# Halfbridge.net
KiCad netlist of a schematic drawn in Altium Designer
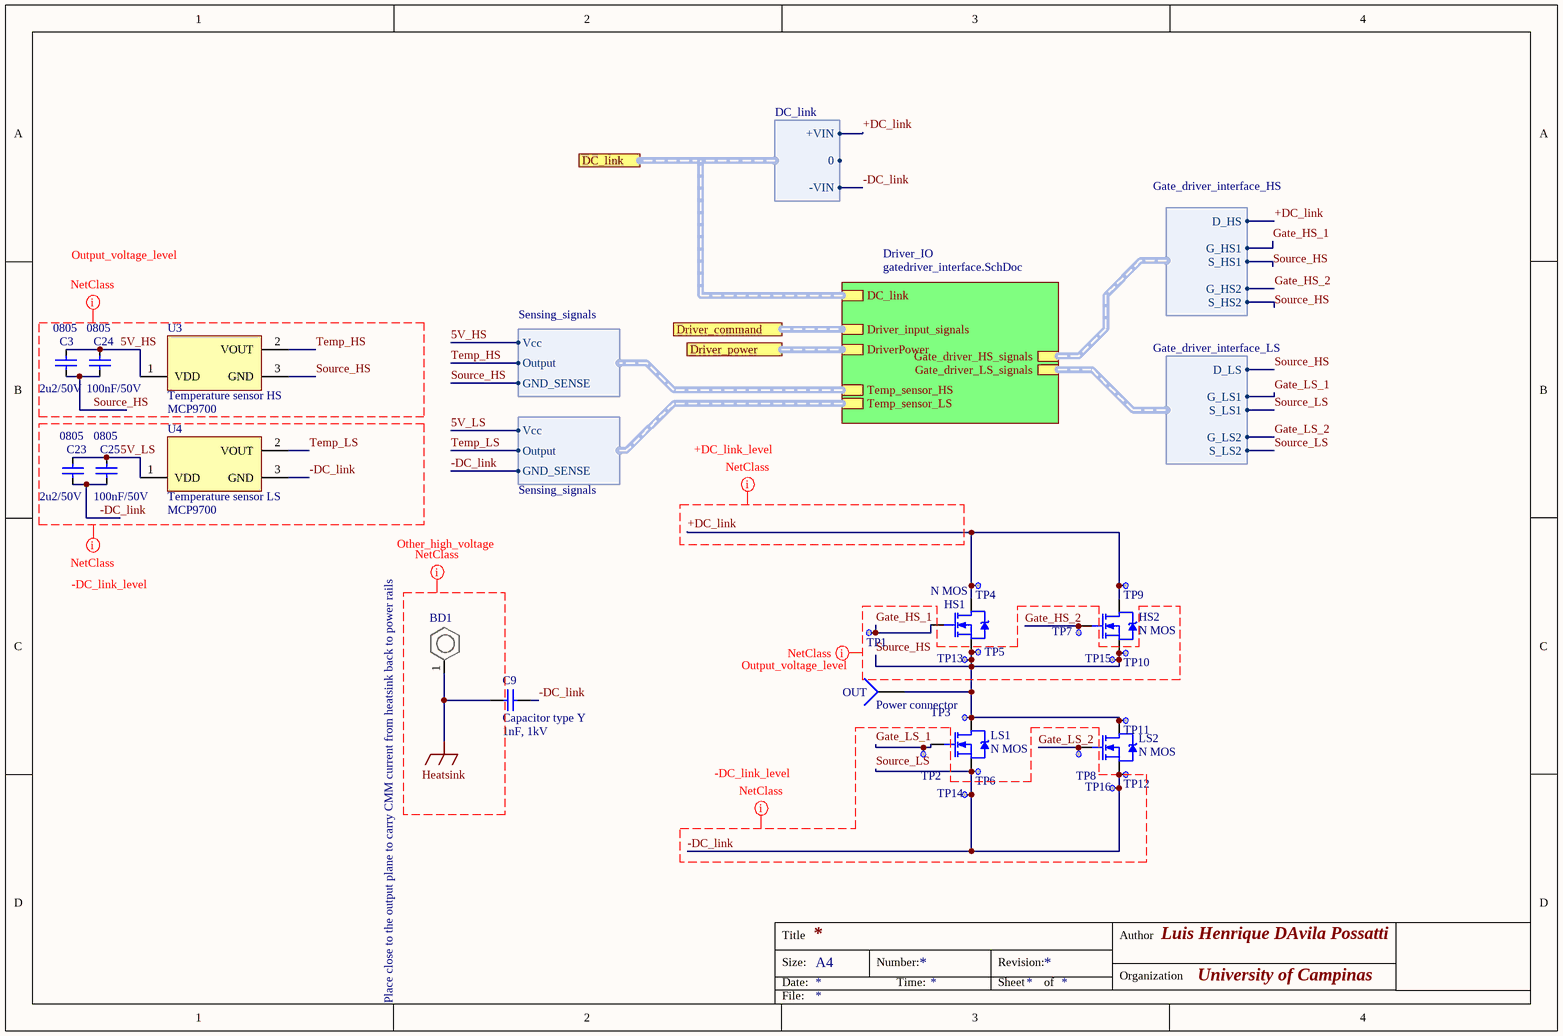
[diagram p0: Halfbridge.SchDoc]

(export (version "E")
  (design (tool "Eeschema 10.0.6"))
  (components
    (comp (ref "BD1")
      (value "Place near output plane")
      (footprint "Bonding_screw")
      (description "Used to connect the net to the heatsink below board")
      (libsource (lib "EdgeInverter_library") (part "Bonding_screw"))
    )
    (comp (ref "C3")
      (value "0805")
      (footprint "Capacitor 0805")
      (description "SMD ceramic capacitor 0805")
      (fields (field (name "ALTIUM_VALUE") "2u2/50V"))
      (libsource (lib "EdgeInverter_library") (part "Capacitor 0805"))
    )
    (comp (ref "C9")
      (value "Capacitor type Y")
      (footprint "CAPACITOR 1812")
      (description "High Voltage Capacitor to filter EMC from heatsink")
      (fields (field (name "ALTIUM_VALUE") "1nF, 1kV"))
      (libsource (lib "EdgeInverter_library") (part "Y Capacitor"))
    )
    (comp (ref "C23")
      (value "0805")
      (footprint "Capacitor 0805")
      (description "SMD ceramic capacitor 0805")
      (fields (field (name "ALTIUM_VALUE") "2u2/50V"))
      (libsource (lib "EdgeInverter_library") (part "Capacitor 0805"))
    )
    (comp (ref "C24")
      (value "0805")
      (footprint "Capacitor 0805")
      (description "SMD ceramic capacitor 0805")
      (fields (field (name "ALTIUM_VALUE") "100nF/50V"))
      (libsource (lib "EdgeInverter_library") (part "Capacitor 0805"))
    )
    (comp (ref "C25")
      (value "0805")
      (footprint "Capacitor 0805")
      (description "SMD ceramic capacitor 0805")
      (fields (field (name "ALTIUM_VALUE") "100nF/50V"))
      (libsource (lib "EdgeInverter_library") (part "Capacitor 0805"))
    )
    (comp (ref "HS1")
      (value "N MOS")
      (footprint "TO247 custom 4")
      (description "Power Mosfet N channel, TO-247, multiple part numbers")
      (libsource (lib "EdgeInverter_library") (part "MOSFET"))
    )
    (comp (ref "HS2")
      (value "N MOS")
      (footprint "TO247 custom 4")
      (description "Power Mosfet N channel, TO-247, multiple part numbers")
      (libsource (lib "EdgeInverter_library") (part "MOSFET"))
    )
    (comp (ref "LS1")
      (value "N MOS")
      (footprint "TO247 custom 4")
      (description "Power Mosfet N channel, TO-247, multiple part numbers")
      (libsource (lib "EdgeInverter_library") (part "MOSFET"))
    )
    (comp (ref "LS2")
      (value "N MOS")
      (footprint "TO247 custom 4")
      (description "Power Mosfet N channel, TO-247, multiple part numbers")
      (libsource (lib "EdgeInverter_library") (part "MOSFET"))
    )
    (comp (ref "OUT")
      (value "Power connector")
      (footprint "7799 Power Connector")
      (description "TERM SCREW M4 6 PIN PCB")
      (libsource (lib "EdgeInverter_library") (part "Power connector"))
    )
    (comp (ref "TP1")
      (value "Test point")
      (footprint "Test point")
      (description "Test point to probe with oscilloscope")
      (libsource (lib "EdgeInverter_library") (part "Test point"))
    )
    (comp (ref "TP2")
      (value "Test point")
      (footprint "Test point")
      (description "Test point to probe with oscilloscope")
      (libsource (lib "EdgeInverter_library") (part "Test point"))
    )
    (comp (ref "TP3")
      (value "Test point")
      (footprint "Test point")
      (description "Test point to probe with oscilloscope")
      (libsource (lib "EdgeInverter_library") (part "Test point"))
    )
    (comp (ref "TP4")
      (value "Test point")
      (footprint "Test point")
      (description "Test point to probe with oscilloscope")
      (libsource (lib "EdgeInverter_library") (part "Test point"))
    )
    (comp (ref "TP5")
      (value "Test point")
      (footprint "Test point SMD")
      (description "Test point to probe with oscilloscope")
      (libsource (lib "EdgeInverter_library") (part "Test point"))
    )
    (comp (ref "TP6")
      (value "Test point")
      (footprint "Test point")
      (description "Test point to probe with oscilloscope")
      (libsource (lib "EdgeInverter_library") (part "Test point"))
    )
    (comp (ref "TP7")
      (value "Test point")
      (footprint "Test point")
      (description "Test point to probe with oscilloscope")
      (libsource (lib "EdgeInverter_library") (part "Test point"))
    )
    (comp (ref "TP8")
      (value "Test point")
      (footprint "Test point")
      (description "Test point to probe with oscilloscope")
      (libsource (lib "EdgeInverter_library") (part "Test point"))
    )
    (comp (ref "TP9")
      (value "Test point")
      (footprint "Test point")
      (description "Test point to probe with oscilloscope")
      (libsource (lib "EdgeInverter_library") (part "Test point"))
    )
    (comp (ref "TP10")
      (value "Test point")
      (footprint "Test point SMD")
      (description "Test point to probe with oscilloscope")
      (libsource (lib "EdgeInverter_library") (part "Test point"))
    )
    (comp (ref "TP11")
      (value "Test point")
      (footprint "Test point")
      (description "Test point to probe with oscilloscope")
      (libsource (lib "EdgeInverter_library") (part "Test point"))
    )
    (comp (ref "TP12")
      (value "Test point")
      (footprint "Test point")
      (description "Test point to probe with oscilloscope")
      (libsource (lib "EdgeInverter_library") (part "Test point"))
    )
    (comp (ref "TP13")
      (value "Test point")
      (footprint "Test point SMD")
      (description "Test point to probe with oscilloscope")
      (libsource (lib "EdgeInverter_library") (part "Test point"))
    )
    (comp (ref "TP14")
      (value "Test point")
      (footprint "Test point")
      (description "Test point to probe with oscilloscope")
      (libsource (lib "EdgeInverter_library") (part "Test point"))
    )
    (comp (ref "TP15")
      (value "Test point")
      (footprint "Test point SMD")
      (description "Test point to probe with oscilloscope")
      (libsource (lib "EdgeInverter_library") (part "Test point"))
    )
    (comp (ref "TP16")
      (value "Test point")
      (footprint "Test point")
      (description "Test point to probe with oscilloscope")
      (libsource (lib "EdgeInverter_library") (part "Test point"))
    )
    (comp (ref "U3")
      (value "Temperature sensor HS")
      (footprint "SOT 23")
      (description "Low-Power Linear Active Thermistor IC, 3-Pin SOT-23, Extended Temperature, Tape and Reel")
      (fields (field (name "ALTIUM_VALUE") "MCP9700"))
      (libsource (lib "EdgeInverter_library") (part "MCP9700T-E/TT"))
    )
    (comp (ref "U4")
      (value "Temperature sensor LS")
      (footprint "SOT 23")
      (description "Low-Power Linear Active Thermistor IC, 3-Pin SOT-23, Extended Temperature, Tape and Reel")
      (fields (field (name "ALTIUM_VALUE") "MCP9700"))
      (libsource (lib "EdgeInverter_library") (part "MCP9700T-E/TT"))
    )
  )
  (nets
    (net (code "7") (name "/+DC_link") (class "Default")
      (node (ref "HS1") (pin "2") (pinfunction "D_2") (pintype "passive"))
      (node (ref "HS2") (pin "2") (pinfunction "D_2") (pintype "passive"))
      (node (ref "TP4") (pin "1") (pinfunction "1_1") (pintype "passive"))
      (node (ref "TP9") (pin "1") (pinfunction "1_1") (pintype "passive"))
    )
    (net (code "8") (name "/-DC_link") (class "Default")
      (node (ref "C23") (pin "2") (pinfunction "2_2") (pintype "passive"))
      (node (ref "C25") (pin "2") (pinfunction "2_2") (pintype "passive"))
      (node (ref "C9") (pin "2") (pinfunction "2_2") (pintype "passive"))
      (node (ref "LS1") (pin "3") (pinfunction "S_3") (pintype "passive"))
      (node (ref "LS2") (pin "3") (pinfunction "S_3") (pintype "passive"))
      (node (ref "TP12") (pin "1") (pinfunction "1_1") (pintype "passive"))
      (node (ref "TP14") (pin "1") (pinfunction "1_1") (pintype "passive"))
      (node (ref "TP16") (pin "1") (pinfunction "1_1") (pintype "passive"))
      (node (ref "TP6") (pin "1") (pinfunction "1_1") (pintype "passive"))
      (node (ref "U4") (pin "3") (pinfunction "GND_3") (pintype "power_in"))
    )
    (net (code "9") (name "/5V_HS") (class "Default")
      (node (ref "C24") (pin "1") (pinfunction "1_1") (pintype "passive"))
      (node (ref "C3") (pin "1") (pinfunction "1_1") (pintype "passive"))
      (node (ref "U3") (pin "1") (pinfunction "VDD_1") (pintype "power_in"))
    )
    (net (code "10") (name "/5V_LS") (class "Default")
      (node (ref "C23") (pin "1") (pinfunction "1_1") (pintype "passive"))
      (node (ref "C25") (pin "1") (pinfunction "1_1") (pintype "passive"))
      (node (ref "U4") (pin "1") (pinfunction "VDD_1") (pintype "power_in"))
    )
    (net (code "13") (name "/Gate_HS_1") (class "Default")
      (node (ref "HS1") (pin "1") (pinfunction "G_1") (pintype "passive"))
      (node (ref "TP1") (pin "1") (pinfunction "1_1") (pintype "passive"))
    )
    (net (code "14") (name "/Gate_HS_2") (class "Default")
      (node (ref "HS2") (pin "1") (pinfunction "G_1") (pintype "passive"))
      (node (ref "TP7") (pin "1") (pinfunction "1_1") (pintype "passive"))
    )
    (net (code "15") (name "/Gate_LS_1") (class "Default")
      (node (ref "LS1") (pin "1") (pinfunction "G_1") (pintype "passive"))
      (node (ref "TP2") (pin "1") (pinfunction "1_1") (pintype "passive"))
    )
    (net (code "16") (name "/Gate_LS_2") (class "Default")
      (node (ref "LS2") (pin "1") (pinfunction "G_1") (pintype "passive"))
      (node (ref "TP8") (pin "1") (pinfunction "1_1") (pintype "passive"))
    )
    (net (code "17") (name "/Source_HS") (class "Default")
      (node (ref "C24") (pin "2") (pinfunction "2_2") (pintype "passive"))
      (node (ref "C3") (pin "2") (pinfunction "2_2") (pintype "passive"))
      (node (ref "HS1") (pin "3") (pinfunction "S_3") (pintype "passive"))
      (node (ref "HS2") (pin "3") (pinfunction "S_3") (pintype "passive"))
      (node (ref "LS1") (pin "2") (pinfunction "D_2") (pintype "passive"))
      (node (ref "LS2") (pin "2") (pinfunction "D_2") (pintype "passive"))
      (node (ref "OUT") (pin "1") (pinfunction "1_1") (pintype "power_in"))
      (node (ref "TP10") (pin "1") (pinfunction "1_1") (pintype "passive"))
      (node (ref "TP11") (pin "1") (pinfunction "1_1") (pintype "passive"))
      (node (ref "TP13") (pin "1") (pinfunction "1_1") (pintype "passive"))
      (node (ref "TP15") (pin "1") (pinfunction "1_1") (pintype "passive"))
      (node (ref "TP3") (pin "1") (pinfunction "1_1") (pintype "passive"))
      (node (ref "TP5") (pin "1") (pinfunction "1_1") (pintype "passive"))
      (node (ref "U3") (pin "3") (pinfunction "GND_3") (pintype "power_in"))
    )
    (net (code "18") (name "/Temp_HS") (class "Default")
      (node (ref "U3") (pin "2") (pinfunction "VOUT_2") (pintype "power_in"))
    )
    (net (code "19") (name "/Temp_LS") (class "Default")
      (node (ref "U4") (pin "2") (pinfunction "VOUT_2") (pintype "power_in"))
    )
    (net (code "24") (name "Heatsink") (class "Default")
      (node (ref "BD1") (pin "1") (pinfunction "1_1") (pintype "passive"))
      (node (ref "C9") (pin "1") (pinfunction "1_1") (pintype "passive"))
    )
  )
)
